# ECG_and_EMG_V2.net
KiCad netlist of a schematic drawn in EAGLE
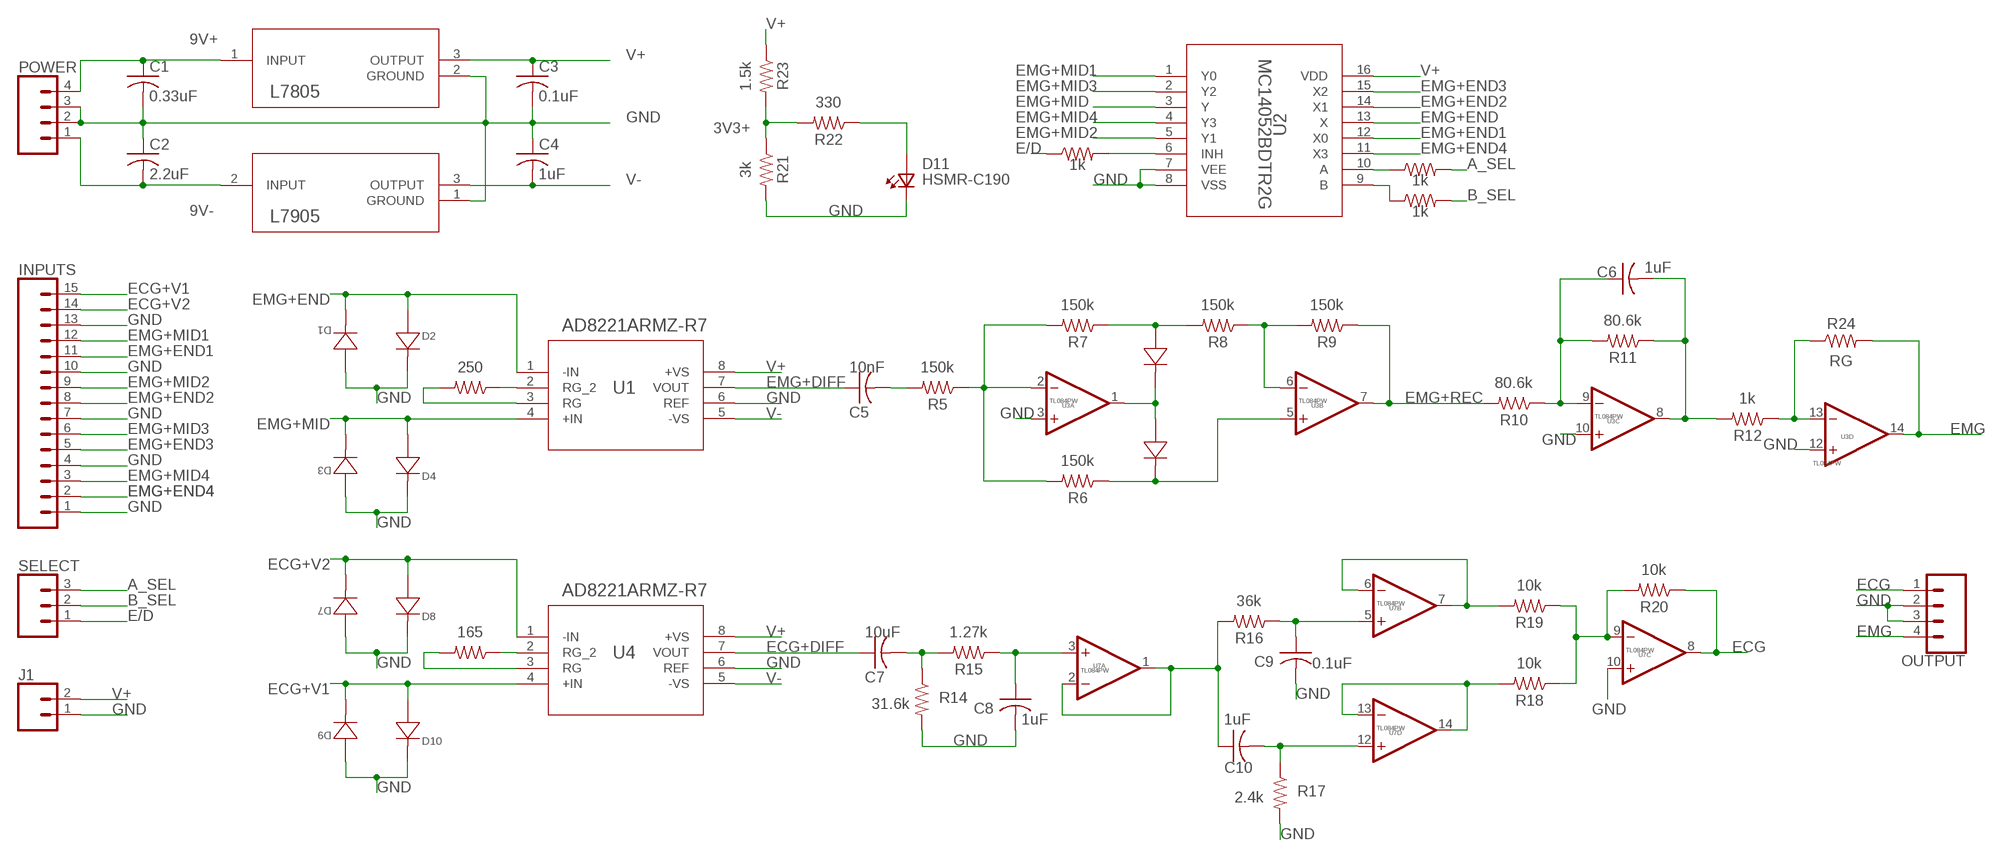
[diagram p0: schematic, sheet 1]

(export (version "E")
  (design (tool "Eeschema 10.0.6"))
  (components
    (comp (ref "C1")
      (value "0.33uF")
      (footprint "eagle-import:CAPC2012X110")
      (libsource (lib "eagle-import") (part "C-USCHIP-0805(2012-METRIC)_"))
    )
    (comp (ref "C2")
      (value "2.2uF")
      (footprint "eagle-import:CAPC2012X110")
      (libsource (lib "eagle-import") (part "C-USCHIP-0805(2012-METRIC)_"))
    )
    (comp (ref "C3")
      (value "0.1uF")
      (footprint "eagle-import:CAPC2012X110")
      (libsource (lib "eagle-import") (part "C-USCHIP-0805(2012-METRIC)_"))
    )
    (comp (ref "C4")
      (value "1uF")
      (footprint "eagle-import:CAPC2012X110")
      (libsource (lib "eagle-import") (part "C-USCHIP-0805(2012-METRIC)_"))
    )
    (comp (ref "C5")
      (value "10nF")
      (footprint "eagle-import:CAPC2012X110")
      (libsource (lib "eagle-import") (part "C-USCHIP-0805(2012-METRIC)_"))
    )
    (comp (ref "C6")
      (value "1uF")
      (footprint "eagle-import:CAPC2012X110")
      (libsource (lib "eagle-import") (part "C-USCHIP-0805(2012-METRIC)_"))
    )
    (comp (ref "C7")
      (value "10uF")
      (footprint "eagle-import:CAPC2012X110")
      (libsource (lib "eagle-import") (part "C-USCHIP-0805(2012-METRIC)_"))
    )
    (comp (ref "C8")
      (value "1uF")
      (footprint "eagle-import:CAPC2012X110")
      (libsource (lib "eagle-import") (part "C-USCHIP-0805(2012-METRIC)_"))
    )
    (comp (ref "C9")
      (value "0.1uF")
      (footprint "eagle-import:CAPC2012X110")
      (libsource (lib "eagle-import") (part "C-USCHIP-0805(2012-METRIC)_"))
    )
    (comp (ref "C10")
      (value "1uF")
      (footprint "eagle-import:CAPC2012X110")
      (libsource (lib "eagle-import") (part "C-USCHIP-0805(2012-METRIC)_"))
    )
    (comp (ref "D1")
      (value "1N4148W-V-GS08SOD123_VIS-L")
      (footprint "eagle-import:SOD123_VIS-L")
      (fields (field (name "MANUFACTURER_PART_NUMBER") "1N4148W-V-GS08"))
      (libsource (lib "eagle-import") (part "1N4148W-V-GS08SOD123_VIS-L"))
    )
    (comp (ref "D2")
      (value "1N4148W-V-GS08SOD123_VIS-L")
      (footprint "eagle-import:SOD123_VIS-L")
      (fields (field (name "MANUFACTURER_PART_NUMBER") "1N4148W-V-GS08"))
      (libsource (lib "eagle-import") (part "1N4148W-V-GS08SOD123_VIS-L"))
    )
    (comp (ref "D3")
      (value "1N4148W-V-GS08SOD123_VIS-L")
      (footprint "eagle-import:SOD123_VIS-L")
      (fields (field (name "MANUFACTURER_PART_NUMBER") "1N4148W-V-GS08"))
      (libsource (lib "eagle-import") (part "1N4148W-V-GS08SOD123_VIS-L"))
    )
    (comp (ref "D4")
      (value "1N4148W-V-GS08SOD123_VIS-L")
      (footprint "eagle-import:SOD123_VIS-L")
      (fields (field (name "MANUFACTURER_PART_NUMBER") "1N4148W-V-GS08"))
      (libsource (lib "eagle-import") (part "1N4148W-V-GS08SOD123_VIS-L"))
    )
    (comp (ref "D5")
      (value "1N4148W-V-GS08SOD123_VIS-L")
      (footprint "eagle-import:SOD123_VIS-L")
      (fields (field (name "MANUFACTURER_PART_NUMBER") "1N4148W-V-GS08"))
      (libsource (lib "eagle-import") (part "1N4148W-V-GS08SOD123_VIS-L"))
    )
    (comp (ref "D6")
      (value "1N4148W-V-GS08SOD123_VIS-L")
      (footprint "eagle-import:SOD123_VIS-L")
      (fields (field (name "MANUFACTURER_PART_NUMBER") "1N4148W-V-GS08"))
      (libsource (lib "eagle-import") (part "1N4148W-V-GS08SOD123_VIS-L"))
    )
    (comp (ref "D7")
      (value "1N4148W-V-GS08SOD123_VIS-L")
      (footprint "eagle-import:SOD123_VIS-L")
      (fields (field (name "MANUFACTURER_PART_NUMBER") "1N4148W-V-GS08"))
      (libsource (lib "eagle-import") (part "1N4148W-V-GS08SOD123_VIS-L"))
    )
    (comp (ref "D8")
      (value "1N4148W-V-GS08SOD123_VIS-L")
      (footprint "eagle-import:SOD123_VIS-L")
      (fields (field (name "MANUFACTURER_PART_NUMBER") "1N4148W-V-GS08"))
      (libsource (lib "eagle-import") (part "1N4148W-V-GS08SOD123_VIS-L"))
    )
    (comp (ref "D9")
      (value "1N4148W-V-GS08SOD123_VIS-L")
      (footprint "eagle-import:SOD123_VIS-L")
      (fields (field (name "MANUFACTURER_PART_NUMBER") "1N4148W-V-GS08"))
      (libsource (lib "eagle-import") (part "1N4148W-V-GS08SOD123_VIS-L"))
    )
    (comp (ref "D10")
      (value "1N4148W-V-GS08SOD123_VIS-L")
      (footprint "eagle-import:SOD123_VIS-L")
      (fields (field (name "MANUFACTURER_PART_NUMBER") "1N4148W-V-GS08"))
      (libsource (lib "eagle-import") (part "1N4148W-V-GS08SOD123_VIS-L"))
    )
    (comp (ref "D11")
      (value "HSMR-C190")
      (footprint "eagle-import:0603")
      (fields (field (name "MF") "Broadcom Limited"))
      (libsource (lib "eagle-import") (part "HSMR-C190"))
    )
    (comp (ref "INPUTS")
      (value "CONN_15")
      (footprint "eagle-import:1X15")
      (libsource (lib "eagle-import") (part "CONN_15"))
    )
    (comp (ref "J1")
      (value "CONN_02")
      (footprint "eagle-import:1X02")
      (libsource (lib "eagle-import") (part "CONN_02"))
    )
    (comp (ref "L7805")
      (value "L7805CD2T-TRD2PAK_STM-M")
      (footprint "eagle-import:D2PAK_STM-M")
      (fields (field (name "MANUFACTURER_PART_NUMBER") "L7805CD2T-TR"))
      (libsource (lib "eagle-import") (part "L7805CD2T-TRD2PAK_STM-M"))
    )
    (comp (ref "L7905")
      (value "L7905ACD2T-TRD2PAK_STM-M")
      (footprint "eagle-import:D2PAK_STM-M")
      (fields (field (name "MANUFACTURER_PART_NUMBER") "L7905ACD2T-TR"))
      (libsource (lib "eagle-import") (part "L7905ACD2T-TRD2PAK_STM-M"))
    )
    (comp (ref "OUTPUT")
      (value "CONN_04")
      (footprint "eagle-import:1X04")
      (libsource (lib "eagle-import") (part "CONN_04"))
    )
    (comp (ref "POWER")
      (value "CONN_04")
      (footprint "eagle-import:1X04")
      (libsource (lib "eagle-import") (part "CONN_04"))
    )
    (comp (ref "R1")
      (value "1k")
      (footprint "eagle-import:RESC2012X65")
      (libsource (lib "eagle-import") (part "R-USCHIP-0805(2012-METRIC)_"))
    )
    (comp (ref "R2")
      (value "1k")
      (footprint "eagle-import:RESC2012X65")
      (libsource (lib "eagle-import") (part "R-USCHIP-0805(2012-METRIC)_"))
    )
    (comp (ref "R3")
      (value "1k")
      (footprint "eagle-import:RESC2012X65")
      (libsource (lib "eagle-import") (part "R-USCHIP-0805(2012-METRIC)_"))
    )
    (comp (ref "R4")
      (value "250")
      (footprint "eagle-import:RESC2012X65")
      (libsource (lib "eagle-import") (part "R-USCHIP-0805(2012-METRIC)_"))
    )
    (comp (ref "R5")
      (value "150k")
      (footprint "eagle-import:RESC2012X65")
      (libsource (lib "eagle-import") (part "R-USCHIP-0805(2012-METRIC)_"))
    )
    (comp (ref "R6")
      (value "150k")
      (footprint "eagle-import:RESC2012X65")
      (libsource (lib "eagle-import") (part "R-USCHIP-0805(2012-METRIC)_"))
    )
    (comp (ref "R7")
      (value "150k")
      (footprint "eagle-import:RESC2012X65")
      (libsource (lib "eagle-import") (part "R-USCHIP-0805(2012-METRIC)_"))
    )
    (comp (ref "R8")
      (value "150k")
      (footprint "eagle-import:RESC2012X65")
      (libsource (lib "eagle-import") (part "R-USCHIP-0805(2012-METRIC)_"))
    )
    (comp (ref "R9")
      (value "150k")
      (footprint "eagle-import:RESC2012X65")
      (libsource (lib "eagle-import") (part "R-USCHIP-0805(2012-METRIC)_"))
    )
    (comp (ref "R10")
      (value "80.6k")
      (footprint "eagle-import:RESC2012X65")
      (libsource (lib "eagle-import") (part "R-USCHIP-0805(2012-METRIC)_"))
    )
    (comp (ref "R11")
      (value "80.6k")
      (footprint "eagle-import:RESC2012X65")
      (libsource (lib "eagle-import") (part "R-USCHIP-0805(2012-METRIC)_"))
    )
    (comp (ref "R12")
      (value "1k")
      (footprint "eagle-import:RESC2012X65")
      (libsource (lib "eagle-import") (part "R-USCHIP-0805(2012-METRIC)_"))
    )
    (comp (ref "R13")
      (value "165")
      (footprint "eagle-import:RESC2012X65")
      (libsource (lib "eagle-import") (part "R-USCHIP-0805(2012-METRIC)_"))
    )
    (comp (ref "R14")
      (value "31.6k")
      (footprint "eagle-import:RESC2012X65")
      (libsource (lib "eagle-import") (part "R-USCHIP-0805(2012-METRIC)_"))
    )
    (comp (ref "R15")
      (value "1.27k")
      (footprint "eagle-import:RESC2012X65")
      (libsource (lib "eagle-import") (part "R-USCHIP-0805(2012-METRIC)_"))
    )
    (comp (ref "R16")
      (value "36k")
      (footprint "eagle-import:RESC2012X65")
      (libsource (lib "eagle-import") (part "R-USCHIP-0805(2012-METRIC)_"))
    )
    (comp (ref "R17")
      (value "2.4k")
      (footprint "eagle-import:RESC2012X65")
      (libsource (lib "eagle-import") (part "R-USCHIP-0805(2012-METRIC)_"))
    )
    (comp (ref "R18")
      (value "10k")
      (footprint "eagle-import:RESC2012X65")
      (libsource (lib "eagle-import") (part "R-USCHIP-0805(2012-METRIC)_"))
    )
    (comp (ref "R19")
      (value "10k")
      (footprint "eagle-import:RESC2012X65")
      (libsource (lib "eagle-import") (part "R-USCHIP-0805(2012-METRIC)_"))
    )
    (comp (ref "R20")
      (value "10k")
      (footprint "eagle-import:RESC2012X65")
      (libsource (lib "eagle-import") (part "R-USCHIP-0805(2012-METRIC)_"))
    )
    (comp (ref "R21")
      (value "3k")
      (footprint "eagle-import:RESC2012X65")
      (libsource (lib "eagle-import") (part "R-USCHIP-0805(2012-METRIC)_"))
    )
    (comp (ref "R22")
      (value "330")
      (footprint "eagle-import:RESC2012X65")
      (libsource (lib "eagle-import") (part "R-USCHIP-0805(2012-METRIC)_"))
    )
    (comp (ref "R23")
      (value "1.5k")
      (footprint "eagle-import:RESC2012X65")
      (libsource (lib "eagle-import") (part "R-USCHIP-0805(2012-METRIC)_"))
    )
    (comp (ref "R24")
      (value "RG")
      (footprint "eagle-import:RESC2012X65")
      (libsource (lib "eagle-import") (part "R-USCHIP-0805(2012-METRIC)_"))
    )
    (comp (ref "SELECT")
      (value "CONN_03")
      (footprint "eagle-import:1X03")
      (libsource (lib "eagle-import") (part "CONN_03"))
    )
    (comp (ref "U1")
      (value "AD8221ARMZ-R7")
      (footprint "eagle-import:RM_8_ADI")
      (libsource (lib "eagle-import") (part "AD8221ARMZ-R7"))
    )
    (comp (ref "U2")
      (value "MC14052BDTR2G")
      (footprint "eagle-import:TSSOP-16_ONS")
      (fields (field (name "COPYRIGHT") "Copyright (C) 2016 Accelerated Designs. All rights reserved"))
      (libsource (lib "eagle-import") (part "MC14052BDTR2G"))
    )
    (comp (ref "U3")
      (value "TL084PW")
      (footprint "eagle-import:TSSOP14")
      (libsource (lib "eagle-import") (part "TL084PW"))
    )
    (comp (ref "U4")
      (value "AD8221ARMZ-R7")
      (footprint "eagle-import:RM_8_ADI")
      (libsource (lib "eagle-import") (part "AD8221ARMZ-R7"))
    )
    (comp (ref "U7")
      (value "TL084PW")
      (footprint "eagle-import:TSSOP14")
      (libsource (lib "eagle-import") (part "TL084PW"))
    )
  )
  (nets
    (net (code "1") (name "/3V3+") (class "Default")
      (node (ref "R21") (pin "1") (pinfunction "1_1") (pintype "passive"))
      (node (ref "R22") (pin "2") (pinfunction "2_2") (pintype "passive"))
      (node (ref "R23") (pin "2") (pinfunction "2_2") (pintype "passive"))
    )
    (net (code "2") (name "/9V+") (class "Default")
      (node (ref "C1") (pin "1") (pinfunction "1_1") (pintype "passive"))
      (node (ref "L7805") (pin "1") (pinfunction "INPUT_1") (pintype "input"))
      (node (ref "POWER") (pin "4") (pinfunction "4_4") (pintype "passive"))
    )
    (net (code "3") (name "/9V-") (class "Default")
      (node (ref "C2") (pin "2") (pinfunction "2_2") (pintype "passive"))
      (node (ref "L7905") (pin "2") (pinfunction "INPUT_2") (pintype "input"))
      (node (ref "POWER") (pin "1") (pinfunction "1_1") (pintype "passive"))
    )
    (net (code "4") (name "/A_SEL") (class "Default")
      (node (ref "R2") (pin "2") (pinfunction "2_2") (pintype "passive"))
      (node (ref "SELECT") (pin "3") (pinfunction "3_3") (pintype "passive"))
    )
    (net (code "5") (name "/B_SEL") (class "Default")
      (node (ref "R3") (pin "2") (pinfunction "2_2") (pintype "passive"))
      (node (ref "SELECT") (pin "2") (pinfunction "2_2") (pintype "passive"))
    )
    (net (code "6") (name "/ECG") (class "Default")
      (node (ref "OUTPUT") (pin "1") (pinfunction "1_1") (pintype "passive"))
      (node (ref "R20") (pin "1") (pinfunction "1_1") (pintype "passive"))
      (node (ref "U7") (pin "8") (pinfunction "OUT_8") (pintype "output"))
    )
    (net (code "7") (name "/ECG+DIFF") (class "Default")
      (node (ref "C7") (pin "1") (pinfunction "1_1") (pintype "passive"))
      (node (ref "U4") (pin "7") (pinfunction "VOUT_7") (pintype "passive"))
    )
    (net (code "8") (name "/ECG+V1") (class "Default")
      (node (ref "D10") (pin "2") (pinfunction "2_2") (pintype "passive"))
      (node (ref "D9") (pin "1") (pinfunction "1_1") (pintype "passive"))
      (node (ref "INPUTS") (pin "15") (pinfunction "15_15") (pintype "passive"))
      (node (ref "U4") (pin "4") (pinfunction "+IN_4") (pintype "passive"))
    )
    (net (code "9") (name "/ECG+V2") (class "Default")
      (node (ref "D7") (pin "1") (pinfunction "1_1") (pintype "passive"))
      (node (ref "D8") (pin "2") (pinfunction "2_2") (pintype "passive"))
      (node (ref "INPUTS") (pin "14") (pinfunction "14_14") (pintype "passive"))
      (node (ref "U4") (pin "1") (pinfunction "-IN_1") (pintype "passive"))
    )
    (net (code "10") (name "/EMG") (class "Default")
      (node (ref "OUTPUT") (pin "4") (pinfunction "4_4") (pintype "passive"))
      (node (ref "R24") (pin "2") (pinfunction "2_2") (pintype "passive"))
      (node (ref "U3") (pin "14") (pinfunction "OUT_14") (pintype "output"))
    )
    (net (code "11") (name "/EMG+DIFF") (class "Default")
      (node (ref "C5") (pin "1") (pinfunction "1_1") (pintype "passive"))
      (node (ref "U1") (pin "7") (pinfunction "VOUT_7") (pintype "passive"))
    )
    (net (code "12") (name "/EMG+END") (class "Default")
      (node (ref "D1") (pin "1") (pinfunction "1_1") (pintype "passive"))
      (node (ref "D2") (pin "2") (pinfunction "2_2") (pintype "passive"))
      (node (ref "U1") (pin "1") (pinfunction "-IN_1") (pintype "passive"))
      (node (ref "U2") (pin "13") (pinfunction "X_13") (pintype "bidirectional"))
    )
    (net (code "13") (name "/EMG+END1") (class "Default")
      (node (ref "INPUTS") (pin "11") (pinfunction "11_11") (pintype "passive"))
      (node (ref "U2") (pin "12") (pinfunction "X0_12") (pintype "bidirectional"))
    )
    (net (code "14") (name "/EMG+END2") (class "Default")
      (node (ref "INPUTS") (pin "8") (pinfunction "8_8") (pintype "passive"))
      (node (ref "U2") (pin "14") (pinfunction "X1_14") (pintype "bidirectional"))
    )
    (net (code "15") (name "/EMG+END3") (class "Default")
      (node (ref "INPUTS") (pin "5") (pinfunction "5_5") (pintype "passive"))
      (node (ref "U2") (pin "15") (pinfunction "X2_15") (pintype "bidirectional"))
    )
    (net (code "16") (name "/EMG+END4") (class "Default")
      (node (ref "INPUTS") (pin "2") (pinfunction "2_2") (pintype "passive"))
      (node (ref "U2") (pin "11") (pinfunction "X3_11") (pintype "bidirectional"))
    )
    (net (code "17") (name "/EMG+MID") (class "Default")
      (node (ref "D3") (pin "1") (pinfunction "1_1") (pintype "passive"))
      (node (ref "D4") (pin "2") (pinfunction "2_2") (pintype "passive"))
      (node (ref "U1") (pin "4") (pinfunction "+IN_4") (pintype "passive"))
      (node (ref "U2") (pin "3") (pinfunction "Y_3") (pintype "bidirectional"))
    )
    (net (code "18") (name "/EMG+MID1") (class "Default")
      (node (ref "INPUTS") (pin "12") (pinfunction "12_12") (pintype "passive"))
      (node (ref "U2") (pin "1") (pinfunction "Y0_1") (pintype "bidirectional"))
    )
    (net (code "19") (name "/EMG+MID2") (class "Default")
      (node (ref "INPUTS") (pin "9") (pinfunction "9_9") (pintype "passive"))
      (node (ref "U2") (pin "5") (pinfunction "Y1_5") (pintype "bidirectional"))
    )
    (net (code "20") (name "/EMG+MID3") (class "Default")
      (node (ref "INPUTS") (pin "6") (pinfunction "6_6") (pintype "passive"))
      (node (ref "U2") (pin "2") (pinfunction "Y2_2") (pintype "bidirectional"))
    )
    (net (code "21") (name "/EMG+MID4") (class "Default")
      (node (ref "INPUTS") (pin "3") (pinfunction "3_3") (pintype "passive"))
      (node (ref "U2") (pin "4") (pinfunction "Y3_4") (pintype "bidirectional"))
    )
    (net (code "22") (name "/EMG+REC") (class "Default")
      (node (ref "R10") (pin "2") (pinfunction "2_2") (pintype "passive"))
      (node (ref "R9") (pin "1") (pinfunction "1_1") (pintype "passive"))
      (node (ref "U3") (pin "7") (pinfunction "OUT_7") (pintype "output"))
    )
    (net (code "23") (name "/E{slash}D") (class "Default")
      (node (ref "R1") (pin "1") (pinfunction "1_1") (pintype "passive"))
      (node (ref "SELECT") (pin "1") (pinfunction "1_1") (pintype "passive"))
    )
    (net (code "24") (name "/GND") (class "Default")
      (node (ref "C1") (pin "2") (pinfunction "2_2") (pintype "passive"))
      (node (ref "C2") (pin "1") (pinfunction "1_1") (pintype "passive"))
      (node (ref "C3") (pin "2") (pinfunction "2_2") (pintype "passive"))
      (node (ref "C4") (pin "1") (pinfunction "1_1") (pintype "passive"))
      (node (ref "C8") (pin "2") (pinfunction "2_2") (pintype "passive"))
      (node (ref "C9") (pin "2") (pinfunction "2_2") (pintype "passive"))
      (node (ref "D1") (pin "2") (pinfunction "2_2") (pintype "passive"))
      (node (ref "D10") (pin "1") (pinfunction "1_1") (pintype "passive"))
      (node (ref "D11") (pin "1") (pinfunction "K2_1") (pintype "passive"))
      (node (ref "D2") (pin "1") (pinfunction "1_1") (pintype "passive"))
      (node (ref "D3") (pin "2") (pinfunction "2_2") (pintype "passive"))
      (node (ref "D4") (pin "1") (pinfunction "1_1") (pintype "passive"))
      (node (ref "D7") (pin "2") (pinfunction "2_2") (pintype "passive"))
      (node (ref "D8") (pin "1") (pinfunction "1_1") (pintype "passive"))
      (node (ref "D9") (pin "2") (pinfunction "2_2") (pintype "passive"))
      (node (ref "INPUTS") (pin "1") (pinfunction "1_1") (pintype "passive"))
      (node (ref "INPUTS") (pin "10") (pinfunction "10_10") (pintype "passive"))
      (node (ref "INPUTS") (pin "13") (pinfunction "13_13") (pintype "passive"))
      (node (ref "INPUTS") (pin "4") (pinfunction "4_4") (pintype "passive"))
      (node (ref "INPUTS") (pin "7") (pinfunction "7_7") (pintype "passive"))
      (node (ref "J1") (pin "1") (pinfunction "1_1") (pintype "passive"))
      (node (ref "L7805") (pin "2") (pinfunction "GROUND_2") (pintype "passive"))
      (node (ref "L7905") (pin "1") (pinfunction "GROUND_1") (pintype "passive"))
      (node (ref "OUTPUT") (pin "2") (pinfunction "2_2") (pintype "passive"))
      (node (ref "OUTPUT") (pin "3") (pinfunction "3_3") (pintype "passive"))
      (node (ref "POWER") (pin "2") (pinfunction "2_2") (pintype "passive"))
      (node (ref "POWER") (pin "3") (pinfunction "3_3") (pintype "passive"))
      (node (ref "R14") (pin "2") (pinfunction "2_2") (pintype "passive"))
      (node (ref "R17") (pin "2") (pinfunction "2_2") (pintype "passive"))
      (node (ref "R21") (pin "2") (pinfunction "2_2") (pintype "passive"))
      (node (ref "U1") (pin "6") (pinfunction "REF_6") (pintype "passive"))
      (node (ref "U2") (pin "7") (pinfunction "VEE_7") (pintype "power_in"))
      (node (ref "U2") (pin "8") (pinfunction "VSS_8") (pintype "power_in"))
      (node (ref "U3") (pin "10") (pinfunction "+IN_10") (pintype "input"))
      (node (ref "U3") (pin "12") (pinfunction "+IN_12") (pintype "input"))
      (node (ref "U3") (pin "3") (pinfunction "+IN_3") (pintype "input"))
      (node (ref "U4") (pin "6") (pinfunction "REF_6") (pintype "passive"))
      (node (ref "U7") (pin "10") (pinfunction "+IN_10") (pintype "input"))
    )
    (net (code "25") (name "/V+") (class "Default")
      (node (ref "C3") (pin "1") (pinfunction "1_1") (pintype "passive"))
      (node (ref "J1") (pin "2") (pinfunction "2_2") (pintype "passive"))
      (node (ref "L7805") (pin "3") (pinfunction "OUTPUT_3") (pintype "output"))
      (node (ref "R23") (pin "1") (pinfunction "1_1") (pintype "passive"))
      (node (ref "U1") (pin "8") (pinfunction "+VS_8") (pintype "power_in"))
      (node (ref "U2") (pin "16") (pinfunction "VDD_16") (pintype "power_in"))
      (node (ref "U4") (pin "8") (pinfunction "+VS_8") (pintype "power_in"))
    )
    (net (code "26") (name "/V-") (class "Default")
      (node (ref "C4") (pin "2") (pinfunction "2_2") (pintype "passive"))
      (node (ref "L7905") (pin "3") (pinfunction "OUTPUT_3") (pintype "output"))
      (node (ref "U1") (pin "5") (pinfunction "-VS_5") (pintype "power_in"))
      (node (ref "U4") (pin "5") (pinfunction "-VS_5") (pintype "power_in"))
    )
    (net (code "27") (name "Net-(C5-Pad2)") (class "Default")
      (node (ref "C5") (pin "2") (pinfunction "2_2") (pintype "passive"))
      (node (ref "R5") (pin "2") (pinfunction "2_2") (pintype "passive"))
    )
    (net (code "28") (name "Net-(C7-Pad2)") (class "Default")
      (node (ref "C7") (pin "2") (pinfunction "2_2") (pintype "passive"))
      (node (ref "R14") (pin "1") (pinfunction "1_1") (pintype "passive"))
      (node (ref "R15") (pin "2") (pinfunction "2_2") (pintype "passive"))
    )
    (net (code "29") (name "Net-(D5-Pad2)") (class "Default")
      (node (ref "D5") (pin "2") (pinfunction "2_2") (pintype "passive"))
      (node (ref "R7") (pin "1") (pinfunction "1_1") (pintype "passive"))
      (node (ref "R8") (pin "2") (pinfunction "2_2") (pintype "passive"))
    )
    (net (code "30") (name "Net-(D11-A2)") (class "Default")
      (node (ref "D11") (pin "2") (pinfunction "A2_2") (pintype "passive"))
      (node (ref "R22") (pin "1") (pinfunction "1_1") (pintype "passive"))
    )
    (net (code "31") (name "Net-(U1-RG)") (class "Default")
      (node (ref "R4") (pin "2") (pinfunction "2_2") (pintype "passive"))
      (node (ref "U1") (pin "3") (pinfunction "RG_3") (pintype "passive"))
    )
    (net (code "32") (name "Net-(U1-RG_2)") (class "Default")
      (node (ref "R4") (pin "1") (pinfunction "1_1") (pintype "passive"))
      (node (ref "U1") (pin "2") (pinfunction "RG_2_2") (pintype "passive"))
    )
    (net (code "33") (name "Net-(U2-A)") (class "Default")
      (node (ref "R2") (pin "1") (pinfunction "1_1") (pintype "passive"))
      (node (ref "U2") (pin "10") (pinfunction "A_10") (pintype "input"))
    )
    (net (code "34") (name "Net-(U2-B)") (class "Default")
      (node (ref "R3") (pin "1") (pinfunction "1_1") (pintype "passive"))
      (node (ref "U2") (pin "9") (pinfunction "B_9") (pintype "input"))
    )
    (net (code "35") (name "Net-(U2-INH)") (class "Default")
      (node (ref "R1") (pin "2") (pinfunction "2_2") (pintype "passive"))
      (node (ref "U2") (pin "6") (pinfunction "INH_6") (pintype "input"))
    )
    (net (code "36") (name "Net-(U3A--IN)") (class "Default")
      (node (ref "R5") (pin "1") (pinfunction "1_1") (pintype "passive"))
      (node (ref "R6") (pin "2") (pinfunction "2_2") (pintype "passive"))
      (node (ref "R7") (pin "2") (pinfunction "2_2") (pintype "passive"))
      (node (ref "U3") (pin "2") (pinfunction "-IN_2") (pintype "input"))
    )
    (net (code "37") (name "Net-(U3A-OUT)") (class "Default")
      (node (ref "D5") (pin "1") (pinfunction "1_1") (pintype "passive"))
      (node (ref "D6") (pin "2") (pinfunction "2_2") (pintype "passive"))
      (node (ref "U3") (pin "1") (pinfunction "OUT_1") (pintype "output"))
    )
    (net (code "38") (name "Net-(U3B-+IN)") (class "Default")
      (node (ref "D6") (pin "1") (pinfunction "1_1") (pintype "passive"))
      (node (ref "R6") (pin "1") (pinfunction "1_1") (pintype "passive"))
      (node (ref "U3") (pin "5") (pinfunction "+IN_5") (pintype "input"))
    )
    (net (code "39") (name "Net-(U3B--IN)") (class "Default")
      (node (ref "R8") (pin "1") (pinfunction "1_1") (pintype "passive"))
      (node (ref "R9") (pin "2") (pinfunction "2_2") (pintype "passive"))
      (node (ref "U3") (pin "6") (pinfunction "-IN_6") (pintype "input"))
    )
    (net (code "40") (name "Net-(U3C--IN)") (class "Default")
      (node (ref "C6") (pin "1") (pinfunction "1_1") (pintype "passive"))
      (node (ref "R10") (pin "1") (pinfunction "1_1") (pintype "passive"))
      (node (ref "R11") (pin "2") (pinfunction "2_2") (pintype "passive"))
      (node (ref "U3") (pin "9") (pinfunction "-IN_9") (pintype "input"))
    )
    (net (code "41") (name "Net-(U3C-OUT)") (class "Default")
      (node (ref "C6") (pin "2") (pinfunction "2_2") (pintype "passive"))
      (node (ref "R11") (pin "1") (pinfunction "1_1") (pintype "passive"))
      (node (ref "R12") (pin "2") (pinfunction "2_2") (pintype "passive"))
      (node (ref "U3") (pin "8") (pinfunction "OUT_8") (pintype "output"))
    )
    (net (code "42") (name "Net-(U3D--IN)") (class "Default")
      (node (ref "R12") (pin "1") (pinfunction "1_1") (pintype "passive"))
      (node (ref "R24") (pin "1") (pinfunction "1_1") (pintype "passive"))
      (node (ref "U3") (pin "13") (pinfunction "-IN_13") (pintype "input"))
    )
    (net (code "43") (name "Net-(U4-RG)") (class "Default")
      (node (ref "R13") (pin "2") (pinfunction "2_2") (pintype "passive"))
      (node (ref "U4") (pin "3") (pinfunction "RG_3") (pintype "passive"))
    )
    (net (code "44") (name "Net-(U4-RG_2)") (class "Default")
      (node (ref "R13") (pin "1") (pinfunction "1_1") (pintype "passive"))
      (node (ref "U4") (pin "2") (pinfunction "RG_2_2") (pintype "passive"))
    )
    (net (code "45") (name "Net-(U7A-+IN)") (class "Default")
      (node (ref "C8") (pin "1") (pinfunction "1_1") (pintype "passive"))
      (node (ref "R15") (pin "1") (pinfunction "1_1") (pintype "passive"))
      (node (ref "U7") (pin "3") (pinfunction "+IN_3") (pintype "input"))
    )
    (net (code "46") (name "Net-(U7A--IN)") (class "Default")
      (node (ref "C10") (pin "1") (pinfunction "1_1") (pintype "passive"))
      (node (ref "R16") (pin "2") (pinfunction "2_2") (pintype "passive"))
      (node (ref "U7") (pin "1") (pinfunction "OUT_1") (pintype "output"))
      (node (ref "U7") (pin "2") (pinfunction "-IN_2") (pintype "input"))
    )
    (net (code "47") (name "Net-(U7B-+IN)") (class "Default")
      (node (ref "C9") (pin "1") (pinfunction "1_1") (pintype "passive"))
      (node (ref "R16") (pin "1") (pinfunction "1_1") (pintype "passive"))
      (node (ref "U7") (pin "5") (pinfunction "+IN_5") (pintype "input"))
    )
    (net (code "48") (name "Net-(U7B--IN)") (class "Default")
      (node (ref "R19") (pin "2") (pinfunction "2_2") (pintype "passive"))
      (node (ref "U7") (pin "6") (pinfunction "-IN_6") (pintype "input"))
      (node (ref "U7") (pin "7") (pinfunction "OUT_7") (pintype "output"))
    )
    (net (code "49") (name "Net-(U7C--IN)") (class "Default")
      (node (ref "R18") (pin "1") (pinfunction "1_1") (pintype "passive"))
      (node (ref "R19") (pin "1") (pinfunction "1_1") (pintype "passive"))
      (node (ref "R20") (pin "2") (pinfunction "2_2") (pintype "passive"))
      (node (ref "U7") (pin "9") (pinfunction "-IN_9") (pintype "input"))
    )
    (net (code "50") (name "Net-(U7D-+IN)") (class "Default")
      (node (ref "C10") (pin "2") (pinfunction "2_2") (pintype "passive"))
      (node (ref "R17") (pin "1") (pinfunction "1_1") (pintype "passive"))
      (node (ref "U7") (pin "12") (pinfunction "+IN_12") (pintype "input"))
    )
    (net (code "51") (name "Net-(U7D--IN)") (class "Default")
      (node (ref "R18") (pin "2") (pinfunction "2_2") (pintype "passive"))
      (node (ref "U7") (pin "13") (pinfunction "-IN_13") (pintype "input"))
      (node (ref "U7") (pin "14") (pinfunction "OUT_14") (pintype "output"))
    )
  )
)
